# design.net
KiCad netlist of a schematic drawn in Altium Designer
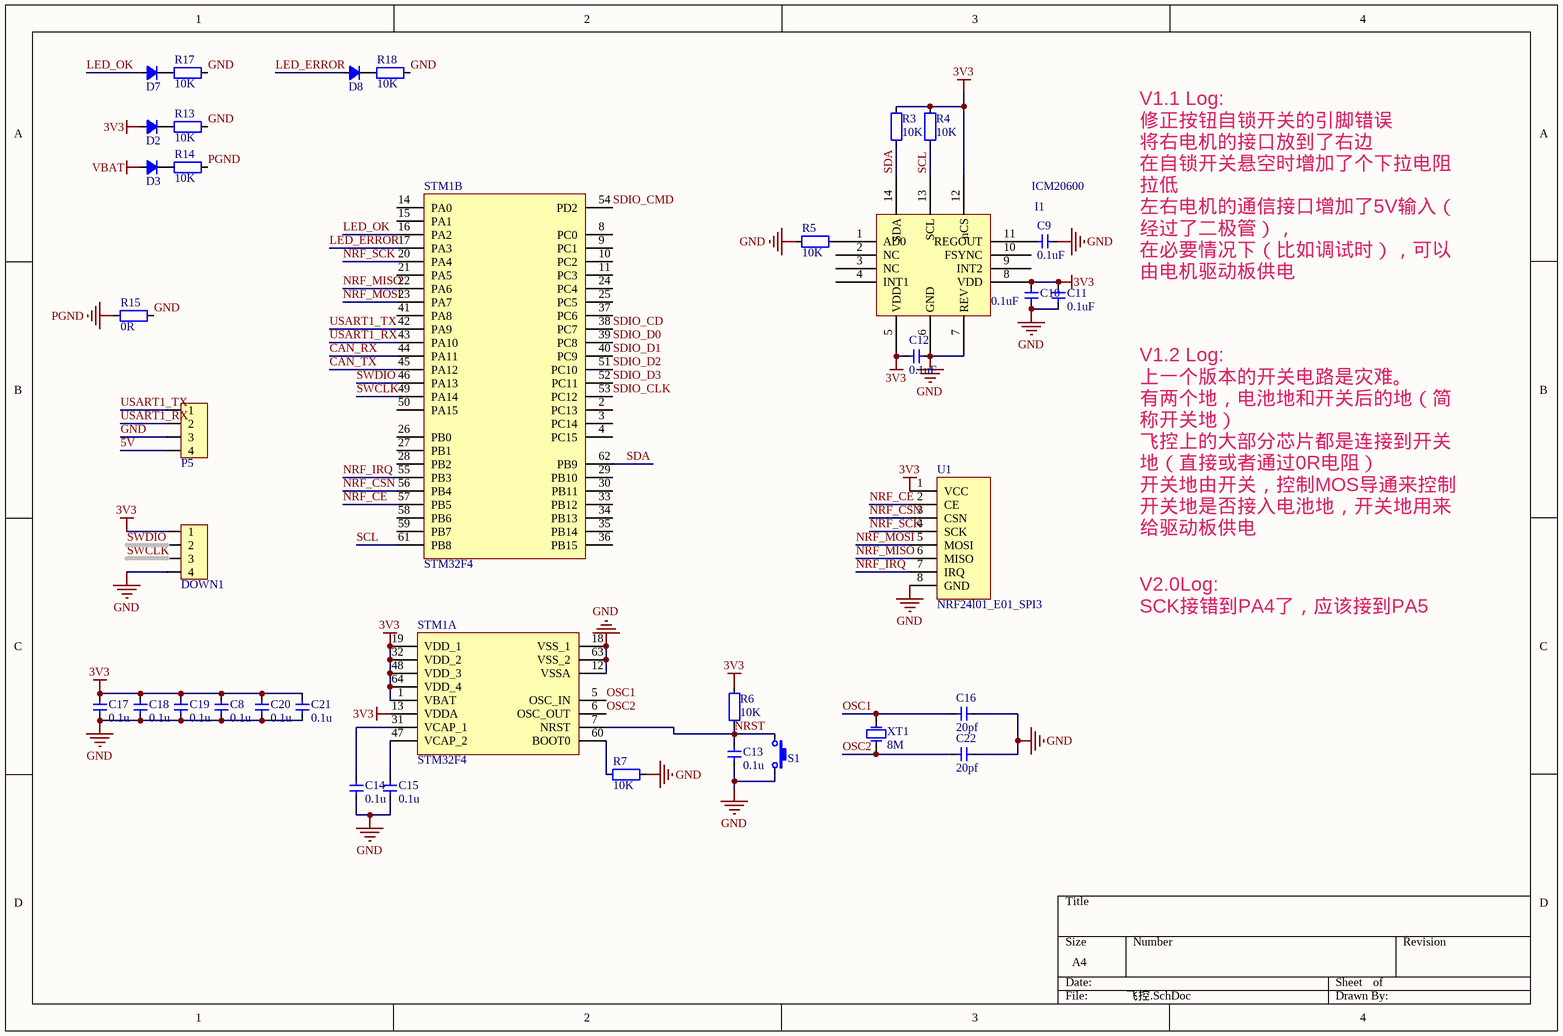
[diagram p0: 飞控.SchDoc]

(export (version "E")
  (design (tool "Eeschema 10.0.6"))
  (components
    (comp (ref "C8")
      (value "0.1u")
      (footprint "PCB_PassiveCap:CAP_0603")
      (description "Capacitor")
      (fields (field (name "Comment") "Cap_0603"))
      (libsource (lib "SCH_Passive") (part "Cap_0603"))
    )
    (comp (ref "C9")
      (value "0.1uF")
      (footprint "PCB_PassiveCap:CAP_0603")
      (description "Capacitor")
      (fields (field (name "Comment") "Cap_0603"))
      (libsource (lib "SCH_Passive") (part "Cap_0603"))
    )
    (comp (ref "C10")
      (value "0.1uF")
      (footprint "PCB_PassiveCap:CAP_0603")
      (description "Capacitor")
      (fields (field (name "Comment") "Cap_0603"))
      (libsource (lib "SCH_Passive") (part "Cap_0603"))
    )
    (comp (ref "C11")
      (value "0.1uF")
      (footprint "PCB_PassiveCap:CAP_0603")
      (description "Capacitor")
      (fields (field (name "Comment") "Cap_0603"))
      (libsource (lib "SCH_Passive") (part "Cap_0603"))
    )
    (comp (ref "C12")
      (value "0.1uF")
      (footprint "PCB_PassiveCap:CAP_0603")
      (description "Capacitor")
      (fields (field (name "Comment") "Cap_0603"))
      (libsource (lib "SCH_Passive") (part "Cap_0603"))
    )
    (comp (ref "C13")
      (value "0.1u")
      (footprint "PCB_PassiveCap:CAP_0603")
      (description "Capacitor")
      (fields (field (name "Comment") "Cap_0603"))
      (libsource (lib "SCH_Passive") (part "Cap_0603"))
    )
    (comp (ref "C14")
      (value "0.1u")
      (footprint "PCB_PassiveCap:CAP_0603")
      (description "Capacitor")
      (fields (field (name "Comment") "Cap_0603"))
      (libsource (lib "SCH_Passive") (part "Cap_0603"))
    )
    (comp (ref "C15")
      (value "0.1u")
      (footprint "PCB_PassiveCap:CAP_0603")
      (description "Capacitor")
      (fields (field (name "Comment") "Cap_0603"))
      (libsource (lib "SCH_Passive") (part "Cap_0603"))
    )
    (comp (ref "C16")
      (value "20pf")
      (footprint "PCB_PassiveCap:CAP_0603")
      (description "Capacitor")
      (fields (field (name "Comment") "Cap_0603"))
      (libsource (lib "SCH_Passive") (part "Cap_0603"))
    )
    (comp (ref "C17")
      (value "0.1u")
      (footprint "PCB_PassiveCap:CAP_0603")
      (description "Capacitor")
      (fields (field (name "Comment") "Cap_0603"))
      (libsource (lib "SCH_Passive") (part "Cap_0603"))
    )
    (comp (ref "C18")
      (value "0.1u")
      (footprint "PCB_PassiveCap:CAP_0603")
      (description "Capacitor")
      (fields (field (name "Comment") "Cap_0603"))
      (libsource (lib "SCH_Passive") (part "Cap_0603"))
    )
    (comp (ref "C19")
      (value "0.1u")
      (footprint "PCB_PassiveCap:CAP_0603")
      (description "Capacitor")
      (fields (field (name "Comment") "Cap_0603"))
      (libsource (lib "SCH_Passive") (part "Cap_0603"))
    )
    (comp (ref "C20")
      (value "0.1u")
      (footprint "PCB_PassiveCap:CAP_0603")
      (description "Capacitor")
      (fields (field (name "Comment") "Cap_0603"))
      (libsource (lib "SCH_Passive") (part "Cap_0603"))
    )
    (comp (ref "C21")
      (value "0.1u")
      (footprint "PCB_PassiveCap:CAP_0603")
      (description "Capacitor")
      (fields (field (name "Comment") "Cap_0603"))
      (libsource (lib "SCH_Passive") (part "Cap_0603"))
    )
    (comp (ref "C22")
      (value "20pf")
      (footprint "PCB_PassiveCap:CAP_0603")
      (description "Capacitor")
      (fields (field (name "Comment") "Cap_0603"))
      (libsource (lib "SCH_Passive") (part "Cap_0603"))
    )
    (comp (ref "D2")
      (value "D_0805")
      (footprint "LED_0805_YELLOW")
      (libsource (lib "SCH_Active") (part "D_0805"))
    )
    (comp (ref "D3")
      (value "D_0805")
      (footprint "LED_0805_YELLOW")
      (libsource (lib "SCH_Active") (part "D_0805"))
    )
    (comp (ref "D7")
      (value "D_0805")
      (footprint "LED_0805_YELLOW")
      (libsource (lib "SCH_Active") (part "D_0805"))
    )
    (comp (ref "D8")
      (value "D_0805")
      (footprint "LED_0805_YELLOW")
      (libsource (lib "SCH_Active") (part "D_0805"))
    )
    (comp (ref "DOWN1")
      (value "HDR1x4_2.54")
      (footprint "PCB_ConnectorHDR:HDR1x4_2.54_180")
      (description "Header")
      (libsource (lib "SCH_ConnectorHDR") (part "HDR1x4_2.54"))
    )
    (comp (ref "I1")
      (value "ICM20600")
      (footprint "ICM20600")
      (libsource (lib "SCH_IntegratedCircuit") (part "ICM20600"))
    )
    (comp (ref "P5")
      (value "HDR1x4_2.54")
      (footprint "PCB_ConnectorHDR:HDR1x4_2.54_180")
      (description "Header")
      (libsource (lib "SCH_ConnectorHDR") (part "HDR1x4_2.54"))
    )
    (comp (ref "R3")
      (value "10K")
      (footprint "PCB_PassiveRes:RES_0603")
      (description "Resistor")
      (fields (field (name "Comment") "Res_0603"))
      (libsource (lib "") (part "Res_0603_1"))
    )
    (comp (ref "R4")
      (value "10K")
      (footprint "PCB_PassiveRes:RES_0603")
      (description "Resistor")
      (fields (field (name "Comment") "Res_0603"))
      (libsource (lib "") (part "Res_0603_1"))
    )
    (comp (ref "R5")
      (value "10K")
      (footprint "PCB_PassiveRes:RES_0603")
      (description "Resistor")
      (fields (field (name "Comment") "Res_0603"))
      (libsource (lib "SCH_Passive") (part "Res_0603"))
    )
    (comp (ref "R6")
      (value "10K")
      (footprint "PCB_PassiveRes:RES_0603")
      (description "Resistor")
      (fields (field (name "Comment") "Res_0603"))
      (libsource (lib "") (part "Res_0603_1"))
    )
    (comp (ref "R7")
      (value "10K")
      (footprint "PCB_PassiveRes:RES_0603")
      (description "Resistor")
      (fields (field (name "Comment") "Res_0603"))
      (libsource (lib "SCH_Passive") (part "Res_0603"))
    )
    (comp (ref "R13")
      (value "10K")
      (footprint "PCB_PassiveRes:RES_0603")
      (description "Resistor")
      (fields (field (name "Comment") "Res_0603"))
      (libsource (lib "SCH_Passive") (part "Res_0603"))
    )
    (comp (ref "R14")
      (value "10K")
      (footprint "PCB_PassiveRes:RES_0603")
      (description "Resistor")
      (fields (field (name "Comment") "Res_0603"))
      (libsource (lib "SCH_Passive") (part "Res_0603"))
    )
    (comp (ref "R15")
      (value "0R")
      (footprint "PCB_PassiveRes:RES_0603")
      (description "Resistor")
      (fields (field (name "Comment") "Res_0603"))
      (libsource (lib "SCH_Passive") (part "Res_0603"))
    )
    (comp (ref "R17")
      (value "10K")
      (footprint "PCB_PassiveRes:RES_0603")
      (description "Resistor")
      (fields (field (name "Comment") "Res_0603"))
      (libsource (lib "SCH_Passive") (part "Res_0603"))
    )
    (comp (ref "R18")
      (value "10K")
      (footprint "PCB_PassiveRes:RES_0603")
      (description "Resistor")
      (fields (field (name "Comment") "Res_0603"))
      (libsource (lib "SCH_Passive") (part "Res_0603"))
    )
    (comp (ref "S1")
      (value "ButtonTACT_3x4x2_180")
      (footprint "PCB_Switch:ButtonTACT_3x4x2_180H")
      (description "Button")
      (libsource (lib "SCH_Switch") (part "ButtonTACT_3x4x2_180"))
    )
    (comp (ref "STM1")
      (value "STM32F4")
      (footprint "PCB_IntegratedCircuit:LQFP_P0.5_64")
      (description "MCU")
      (libsource (lib "SCH_IntegratedCircuit") (part "STM32F405R"))
    )
    (comp (ref "U1")
      (value "NRF24l01_E01_SPI3")
      (footprint "E01-ML01SP2")
      (libsource (lib "SCH_Module") (part "NRF24l01_E01_SPI2"))
    )
    (comp (ref "XT1")
      (value "8M")
      (footprint "PCB_Oscillator:XT_5032_2")
      (description "Crystal Oscillator")
      (fields (field (name "Comment") "XTAL_5032_2P"))
      (libsource (lib "SCH_Oscillator") (part "XTAL_5032_2P"))
    )
  )
  (nets
    (net (code "1") (name "/5V") (class "Default")
      (node (ref "P5") (pin "4") (pinfunction "4_4") (pintype "passive"))
    )
    (net (code "2") (name "/CAN_RX") (class "Default")
      (node (ref "STM1") (pin "44") (pinfunction "PA11_44") (pintype "passive"))
    )
    (net (code "3") (name "/CAN_TX") (class "Default")
      (node (ref "STM1") (pin "45") (pinfunction "PA12_45") (pintype "passive"))
    )
    (net (code "4") (name "/LED_ERROR") (class "Default")
      (node (ref "D8") (pin "1") (pinfunction "A_1") (pintype "passive"))
      (node (ref "STM1") (pin "17") (pinfunction "PA3_17") (pintype "passive"))
    )
    (net (code "5") (name "/LED_OK") (class "Default")
      (node (ref "D7") (pin "1") (pinfunction "A_1") (pintype "passive"))
      (node (ref "STM1") (pin "16") (pinfunction "PA2_16") (pintype "passive"))
    )
    (net (code "6") (name "/NRF_CE") (class "Default")
      (node (ref "STM1") (pin "57") (pinfunction "PB5_57") (pintype "passive"))
      (node (ref "U1") (pin "2") (pinfunction "CE_2") (pintype "passive"))
    )
    (net (code "7") (name "/NRF_CSN") (class "Default")
      (node (ref "STM1") (pin "56") (pinfunction "PB4_56") (pintype "passive"))
      (node (ref "U1") (pin "3") (pinfunction "CSN_3") (pintype "passive"))
    )
    (net (code "8") (name "/NRF_IRQ") (class "Default")
      (node (ref "STM1") (pin "55") (pinfunction "PB3_55") (pintype "passive"))
      (node (ref "U1") (pin "7") (pinfunction "IRQ_7") (pintype "passive"))
    )
    (net (code "9") (name "/NRF_MISO") (class "Default")
      (node (ref "STM1") (pin "22") (pinfunction "PA6_22") (pintype "passive"))
      (node (ref "U1") (pin "6") (pinfunction "MISO_6") (pintype "passive"))
    )
    (net (code "10") (name "/NRF_MOSI") (class "Default")
      (node (ref "STM1") (pin "23") (pinfunction "PA7_23") (pintype "passive"))
      (node (ref "U1") (pin "5") (pinfunction "MOSI_5") (pintype "passive"))
    )
    (net (code "11") (name "/NRF_SCK") (class "Default")
      (node (ref "STM1") (pin "20") (pinfunction "PA4_20") (pintype "passive"))
      (node (ref "U1") (pin "4") (pinfunction "SCK_4") (pintype "passive"))
    )
    (net (code "12") (name "/NRST") (class "Default")
      (node (ref "C13") (pin "2") (pinfunction "2_2") (pintype "passive"))
      (node (ref "R6") (pin "2") (pinfunction "2_2") (pintype "passive"))
      (node (ref "S1") (pin "1") (pinfunction "1_1") (pintype "passive"))
      (node (ref "STM1") (pin "7") (pinfunction "NRST_7") (pintype "passive"))
    )
    (net (code "13") (name "/OSC1") (class "Default")
      (node (ref "C16") (pin "2") (pinfunction "2_2") (pintype "passive"))
      (node (ref "STM1") (pin "5") (pinfunction "OSC_IN_5") (pintype "passive"))
      (node (ref "XT1") (pin "2") (pinfunction "OSC2_2") (pintype "passive"))
    )
    (net (code "14") (name "/OSC2") (class "Default")
      (node (ref "C22") (pin "2") (pinfunction "2_2") (pintype "passive"))
      (node (ref "STM1") (pin "6") (pinfunction "OSC_OUT_6") (pintype "passive"))
      (node (ref "XT1") (pin "1") (pinfunction "OSC1_1") (pintype "passive"))
    )
    (net (code "15") (name "/SCL") (class "Default")
      (node (ref "I1") (pin "13") (pinfunction "SCL_13") (pintype "passive"))
      (node (ref "R4") (pin "2") (pinfunction "2_2") (pintype "passive"))
      (node (ref "STM1") (pin "61") (pinfunction "PB8_61") (pintype "passive"))
    )
    (net (code "16") (name "/SDA") (class "Default")
      (node (ref "I1") (pin "14") (pinfunction "SDA_14") (pintype "passive"))
      (node (ref "R3") (pin "2") (pinfunction "2_2") (pintype "passive"))
      (node (ref "STM1") (pin "62") (pinfunction "PB9_62") (pintype "passive"))
    )
    (net (code "17") (name "/SDIO_CD") (class "Default")
      (node (ref "STM1") (pin "38") (pinfunction "PC7_38") (pintype "passive"))
    )
    (net (code "18") (name "/SDIO_CLK") (class "Default")
      (node (ref "STM1") (pin "53") (pinfunction "PC12_53") (pintype "passive"))
    )
    (net (code "19") (name "/SDIO_CMD") (class "Default")
      (node (ref "STM1") (pin "54") (pinfunction "PD2_54") (pintype "passive"))
    )
    (net (code "20") (name "/SDIO_D0") (class "Default")
      (node (ref "STM1") (pin "39") (pinfunction "PC8_39") (pintype "passive"))
    )
    (net (code "21") (name "/SDIO_D1") (class "Default")
      (node (ref "STM1") (pin "40") (pinfunction "PC9_40") (pintype "passive"))
    )
    (net (code "22") (name "/SDIO_D2") (class "Default")
      (node (ref "STM1") (pin "51") (pinfunction "PC10_51") (pintype "passive"))
    )
    (net (code "23") (name "/SDIO_D3") (class "Default")
      (node (ref "STM1") (pin "52") (pinfunction "PC11_52") (pintype "passive"))
    )
    (net (code "24") (name "/SWCLK") (class "Default")
      (node (ref "DOWN1") (pin "3") (pinfunction "3_3") (pintype "passive"))
      (node (ref "STM1") (pin "49") (pinfunction "PA14_49") (pintype "passive"))
    )
    (net (code "25") (name "/SWDIO") (class "Default")
      (node (ref "DOWN1") (pin "2") (pinfunction "2_2") (pintype "passive"))
      (node (ref "STM1") (pin "46") (pinfunction "PA13_46") (pintype "passive"))
    )
    (net (code "26") (name "/USART1_RX") (class "Default")
      (node (ref "P5") (pin "2") (pinfunction "2_2") (pintype "passive"))
      (node (ref "STM1") (pin "43") (pinfunction "PA10_43") (pintype "passive"))
    )
    (net (code "27") (name "/USART1_TX") (class "Default")
      (node (ref "P5") (pin "1") (pinfunction "1_1") (pintype "passive"))
      (node (ref "STM1") (pin "42") (pinfunction "PA9_42") (pintype "passive"))
    )
    (net (code "28") (name "3V3") (class "Default")
      (node (ref "C10") (pin "1") (pinfunction "1_1") (pintype "passive"))
      (node (ref "C11") (pin "1") (pinfunction "1_1") (pintype "passive"))
      (node (ref "C12") (pin "2") (pinfunction "2_2") (pintype "passive"))
      (node (ref "C17") (pin "2") (pinfunction "2_2") (pintype "passive"))
      (node (ref "C18") (pin "2") (pinfunction "2_2") (pintype "passive"))
      (node (ref "C19") (pin "2") (pinfunction "2_2") (pintype "passive"))
      (node (ref "C20") (pin "2") (pinfunction "2_2") (pintype "passive"))
      (node (ref "C21") (pin "2") (pinfunction "2_2") (pintype "passive"))
      (node (ref "C8") (pin "2") (pinfunction "2_2") (pintype "passive"))
      (node (ref "D2") (pin "1") (pinfunction "A_1") (pintype "passive"))
      (node (ref "DOWN1") (pin "1") (pinfunction "1_1") (pintype "passive"))
      (node (ref "I1") (pin "12") (pinfunction "nCS_12") (pintype "passive"))
      (node (ref "I1") (pin "5") (pinfunction "VDD_5") (pintype "passive"))
      (node (ref "I1") (pin "8") (pinfunction "VDD_8") (pintype "passive"))
      (node (ref "R3") (pin "1") (pinfunction "1_1") (pintype "passive"))
      (node (ref "R4") (pin "1") (pinfunction "1_1") (pintype "passive"))
      (node (ref "R6") (pin "1") (pinfunction "1_1") (pintype "passive"))
      (node (ref "STM1") (pin "1") (pinfunction "VBAT_1") (pintype "passive"))
      (node (ref "STM1") (pin "13") (pinfunction "VDDA_13") (pintype "passive"))
      (node (ref "STM1") (pin "19") (pinfunction "VDD_1_19") (pintype "passive"))
      (node (ref "STM1") (pin "32") (pinfunction "VDD_2_32") (pintype "passive"))
      (node (ref "STM1") (pin "48") (pinfunction "VDD_3_48") (pintype "passive"))
      (node (ref "STM1") (pin "64") (pinfunction "VDD_4_64") (pintype "passive"))
      (node (ref "U1") (pin "1") (pinfunction "VCC_1") (pintype "passive"))
    )
    (net (code "29") (name "GND") (class "Default")
      (node (ref "C10") (pin "2") (pinfunction "2_2") (pintype "passive"))
      (node (ref "C11") (pin "2") (pinfunction "2_2") (pintype "passive"))
      (node (ref "C12") (pin "1") (pinfunction "1_1") (pintype "passive"))
      (node (ref "C13") (pin "1") (pinfunction "1_1") (pintype "passive"))
      (node (ref "C14") (pin "2") (pinfunction "2_2") (pintype "passive"))
      (node (ref "C15") (pin "2") (pinfunction "2_2") (pintype "passive"))
      (node (ref "C16") (pin "1") (pinfunction "1_1") (pintype "passive"))
      (node (ref "C17") (pin "1") (pinfunction "1_1") (pintype "passive"))
      (node (ref "C18") (pin "1") (pinfunction "1_1") (pintype "passive"))
      (node (ref "C19") (pin "1") (pinfunction "1_1") (pintype "passive"))
      (node (ref "C20") (pin "1") (pinfunction "1_1") (pintype "passive"))
      (node (ref "C21") (pin "1") (pinfunction "1_1") (pintype "passive"))
      (node (ref "C22") (pin "1") (pinfunction "1_1") (pintype "passive"))
      (node (ref "C8") (pin "1") (pinfunction "1_1") (pintype "passive"))
      (node (ref "C9") (pin "2") (pinfunction "2_2") (pintype "passive"))
      (node (ref "DOWN1") (pin "4") (pinfunction "4_4") (pintype "passive"))
      (node (ref "I1") (pin "6") (pinfunction "GND_6") (pintype "passive"))
      (node (ref "I1") (pin "7") (pinfunction "REV_7") (pintype "passive"))
      (node (ref "P5") (pin "3") (pinfunction "3_3") (pintype "passive"))
      (node (ref "R13") (pin "2") (pinfunction "2_2") (pintype "passive"))
      (node (ref "R15") (pin "2") (pinfunction "2_2") (pintype "passive"))
      (node (ref "R17") (pin "2") (pinfunction "2_2") (pintype "passive"))
      (node (ref "R18") (pin "2") (pinfunction "2_2") (pintype "passive"))
      (node (ref "R5") (pin "1") (pinfunction "1_1") (pintype "passive"))
      (node (ref "R7") (pin "2") (pinfunction "2_2") (pintype "passive"))
      (node (ref "S1") (pin "2") (pinfunction "2_2") (pintype "passive"))
      (node (ref "STM1") (pin "12") (pinfunction "VSSA_12") (pintype "passive"))
      (node (ref "STM1") (pin "18") (pinfunction "VSS_1_18") (pintype "passive"))
      (node (ref "STM1") (pin "63") (pinfunction "VSS_2_63") (pintype "passive"))
      (node (ref "U1") (pin "8") (pinfunction "GND_8") (pintype "passive"))
    )
    (net (code "30") (name "Net-(D2-K)") (class "Default")
      (node (ref "D2") (pin "2") (pinfunction "K_2") (pintype "passive"))
      (node (ref "R13") (pin "1") (pinfunction "1_1") (pintype "passive"))
    )
    (net (code "31") (name "Net-(D3-K)") (class "Default")
      (node (ref "D3") (pin "2") (pinfunction "K_2") (pintype "passive"))
      (node (ref "R14") (pin "1") (pinfunction "1_1") (pintype "passive"))
    )
    (net (code "32") (name "Net-(D7-K)") (class "Default")
      (node (ref "D7") (pin "2") (pinfunction "K_2") (pintype "passive"))
      (node (ref "R17") (pin "1") (pinfunction "1_1") (pintype "passive"))
    )
    (net (code "33") (name "Net-(D8-K)") (class "Default")
      (node (ref "D8") (pin "2") (pinfunction "K_2") (pintype "passive"))
      (node (ref "R18") (pin "1") (pinfunction "1_1") (pintype "passive"))
    )
    (net (code "34") (name "Net-(I1-AD0)") (class "Default")
      (node (ref "I1") (pin "1") (pinfunction "AD0_1") (pintype "passive"))
      (node (ref "R5") (pin "2") (pinfunction "2_2") (pintype "passive"))
    )
    (net (code "35") (name "Net-(I1-REGOUT)") (class "Default")
      (node (ref "C9") (pin "1") (pinfunction "1_1") (pintype "passive"))
      (node (ref "I1") (pin "11") (pinfunction "REGOUT_11") (pintype "passive"))
    )
    (net (code "36") (name "Net-(STM1A-BOOT0)") (class "Default")
      (node (ref "R7") (pin "1") (pinfunction "1_1") (pintype "passive"))
      (node (ref "STM1") (pin "60") (pinfunction "BOOT0_60") (pintype "passive"))
    )
    (net (code "37") (name "Net-(STM1A-VCAP_1)") (class "Default")
      (node (ref "C14") (pin "1") (pinfunction "1_1") (pintype "passive"))
      (node (ref "STM1") (pin "31") (pinfunction "VCAP_1_31") (pintype "passive"))
    )
    (net (code "38") (name "Net-(STM1A-VCAP_2)") (class "Default")
      (node (ref "C15") (pin "1") (pinfunction "1_1") (pintype "passive"))
      (node (ref "STM1") (pin "47") (pinfunction "VCAP_2_47") (pintype "passive"))
    )
    (net (code "39") (name "PGND") (class "Default")
      (node (ref "R14") (pin "2") (pinfunction "2_2") (pintype "passive"))
      (node (ref "R15") (pin "1") (pinfunction "1_1") (pintype "passive"))
    )
    (net (code "40") (name "VBAT") (class "Default")
      (node (ref "D3") (pin "1") (pinfunction "A_1") (pintype "passive"))
    )
    (net (code "41") (name "unconnected-(I1-FSYNC-Pad10)") (class "Default")
      (node (ref "I1") (pin "10") (pinfunction "FSYNC_10") (pintype "passive"))
    )
    (net (code "42") (name "unconnected-(I1-INT1-Pad4)") (class "Default")
      (node (ref "I1") (pin "4") (pinfunction "INT1_4") (pintype "passive"))
    )
    (net (code "43") (name "unconnected-(I1-INT2-Pad9)") (class "Default")
      (node (ref "I1") (pin "9") (pinfunction "INT2_9") (pintype "passive"))
    )
    (net (code "44") (name "unconnected-(I1-NC-Pad2)") (class "Default")
      (node (ref "I1") (pin "2") (pinfunction "NC_2") (pintype "passive"))
    )
    (net (code "45") (name "unconnected-(I1-NC-Pad3)") (class "Default")
      (node (ref "I1") (pin "3") (pinfunction "NC_3") (pintype "passive"))
    )
    (net (code "46") (name "unconnected-(STM1B-PA0-Pad14)") (class "Default")
      (node (ref "STM1") (pin "14") (pinfunction "PA0_14") (pintype "passive"))
    )
    (net (code "47") (name "unconnected-(STM1B-PA1-Pad15)") (class "Default")
      (node (ref "STM1") (pin "15") (pinfunction "PA1_15") (pintype "passive"))
    )
    (net (code "48") (name "unconnected-(STM1B-PA5-Pad21)") (class "Default")
      (node (ref "STM1") (pin "21") (pinfunction "PA5_21") (pintype "passive"))
    )
    (net (code "49") (name "unconnected-(STM1B-PA8-Pad41)") (class "Default")
      (node (ref "STM1") (pin "41") (pinfunction "PA8_41") (pintype "passive"))
    )
    (net (code "50") (name "unconnected-(STM1B-PA15-Pad50)") (class "Default")
      (node (ref "STM1") (pin "50") (pinfunction "PA15_50") (pintype "passive"))
    )
    (net (code "51") (name "unconnected-(STM1B-PB0-Pad26)") (class "Default")
      (node (ref "STM1") (pin "26") (pinfunction "PB0_26") (pintype "passive"))
    )
    (net (code "52") (name "unconnected-(STM1B-PB1-Pad27)") (class "Default")
      (node (ref "STM1") (pin "27") (pinfunction "PB1_27") (pintype "passive"))
    )
    (net (code "53") (name "unconnected-(STM1B-PB2-Pad28)") (class "Default")
      (node (ref "STM1") (pin "28") (pinfunction "PB2_28") (pintype "passive"))
    )
    (net (code "54") (name "unconnected-(STM1B-PB6-Pad58)") (class "Default")
      (node (ref "STM1") (pin "58") (pinfunction "PB6_58") (pintype "passive"))
    )
    (net (code "55") (name "unconnected-(STM1B-PB7-Pad59)") (class "Default")
      (node (ref "STM1") (pin "59") (pinfunction "PB7_59") (pintype "passive"))
    )
    (net (code "56") (name "unconnected-(STM1B-PB10-Pad29)") (class "Default")
      (node (ref "STM1") (pin "29") (pinfunction "PB10_29") (pintype "passive"))
    )
    (net (code "57") (name "unconnected-(STM1B-PB11-Pad30)") (class "Default")
      (node (ref "STM1") (pin "30") (pinfunction "PB11_30") (pintype "passive"))
    )
    (net (code "58") (name "unconnected-(STM1B-PB12-Pad33)") (class "Default")
      (node (ref "STM1") (pin "33") (pinfunction "PB12_33") (pintype "passive"))
    )
    (net (code "59") (name "unconnected-(STM1B-PB13-Pad34)") (class "Default")
      (node (ref "STM1") (pin "34") (pinfunction "PB13_34") (pintype "passive"))
    )
    (net (code "60") (name "unconnected-(STM1B-PB14-Pad35)") (class "Default")
      (node (ref "STM1") (pin "35") (pinfunction "PB14_35") (pintype "passive"))
    )
    (net (code "61") (name "unconnected-(STM1B-PB15-Pad36)") (class "Default")
      (node (ref "STM1") (pin "36") (pinfunction "PB15_36") (pintype "passive"))
    )
    (net (code "62") (name "unconnected-(STM1B-PC0-Pad8)") (class "Default")
      (node (ref "STM1") (pin "8") (pinfunction "PC0_8") (pintype "passive"))
    )
    (net (code "63") (name "unconnected-(STM1B-PC1-Pad9)") (class "Default")
      (node (ref "STM1") (pin "9") (pinfunction "PC1_9") (pintype "passive"))
    )
    (net (code "64") (name "unconnected-(STM1B-PC2-Pad10)") (class "Default")
      (node (ref "STM1") (pin "10") (pinfunction "PC2_10") (pintype "passive"))
    )
    (net (code "65") (name "unconnected-(STM1B-PC3-Pad11)") (class "Default")
      (node (ref "STM1") (pin "11") (pinfunction "PC3_11") (pintype "passive"))
    )
    (net (code "66") (name "unconnected-(STM1B-PC4-Pad24)") (class "Default")
      (node (ref "STM1") (pin "24") (pinfunction "PC4_24") (pintype "passive"))
    )
    (net (code "67") (name "unconnected-(STM1B-PC5-Pad25)") (class "Default")
      (node (ref "STM1") (pin "25") (pinfunction "PC5_25") (pintype "passive"))
    )
    (net (code "68") (name "unconnected-(STM1B-PC6-Pad37)") (class "Default")
      (node (ref "STM1") (pin "37") (pinfunction "PC6_37") (pintype "passive"))
    )
    (net (code "69") (name "unconnected-(STM1B-PC13-Pad2)") (class "Default")
      (node (ref "STM1") (pin "2") (pinfunction "PC13_2") (pintype "passive"))
    )
    (net (code "70") (name "unconnected-(STM1B-PC14-Pad3)") (class "Default")
      (node (ref "STM1") (pin "3") (pinfunction "PC14_3") (pintype "passive"))
    )
    (net (code "71") (name "unconnected-(STM1B-PC15-Pad4)") (class "Default")
      (node (ref "STM1") (pin "4") (pinfunction "PC15_4") (pintype "passive"))
    )
  )
)
